# anti1_bot.net
KiCad netlist of a schematic drawn in EAGLE
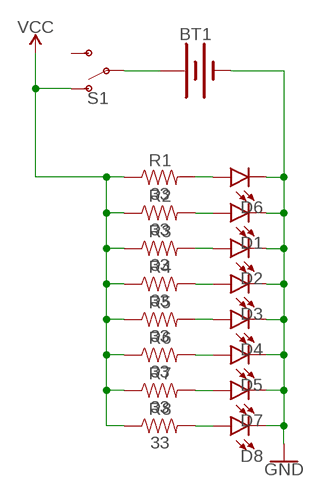
[diagram p0: schematic, sheet 1]

(export (version "E")
  (design (tool "Eeschema 10.0.6"))
  (components
    (comp (ref "BT1")
      (value "BATTERY-20MM_SMD_4LEGS")
      (footprint "eagle-import:BATTCON_20MM_4LEGS")
      (libsource (lib "eagle-import") (part "BATTERY-20MM_SMD_4LEGS"))
    )
    (comp (ref "D1")
      (value "LED0603")
      (footprint "eagle-import:LED-0603")
      (libsource (lib "eagle-import") (part "LED0603"))
    )
    (comp (ref "D2")
      (value "LED0603")
      (footprint "eagle-import:LED-0603")
      (libsource (lib "eagle-import") (part "LED0603"))
    )
    (comp (ref "D3")
      (value "LED0603")
      (footprint "eagle-import:LED-0603")
      (libsource (lib "eagle-import") (part "LED0603"))
    )
    (comp (ref "D4")
      (value "LED0603")
      (footprint "eagle-import:LED-0603")
      (libsource (lib "eagle-import") (part "LED0603"))
    )
    (comp (ref "D5")
      (value "LED0603")
      (footprint "eagle-import:LED-0603")
      (libsource (lib "eagle-import") (part "LED0603"))
    )
    (comp (ref "D6")
      (value "LED0603")
      (footprint "eagle-import:LED-0603")
      (libsource (lib "eagle-import") (part "LED0603"))
    )
    (comp (ref "D7")
      (value "LED0603")
      (footprint "eagle-import:LED-0603")
      (libsource (lib "eagle-import") (part "LED0603"))
    )
    (comp (ref "D8")
      (value "LED0603")
      (footprint "eagle-import:LED-0603")
      (libsource (lib "eagle-import") (part "LED0603"))
    )
    (comp (ref "R1")
      (value "33")
      (footprint "eagle-import:0603")
      (libsource (lib "eagle-import") (part "33OHM-0603-1/10W-1%"))
    )
    (comp (ref "R2")
      (value "33")
      (footprint "eagle-import:0603")
      (libsource (lib "eagle-import") (part "33OHM-0603-1/10W-1%"))
    )
    (comp (ref "R3")
      (value "33")
      (footprint "eagle-import:0603")
      (libsource (lib "eagle-import") (part "33OHM-0603-1/10W-1%"))
    )
    (comp (ref "R4")
      (value "33")
      (footprint "eagle-import:0603")
      (libsource (lib "eagle-import") (part "33OHM-0603-1/10W-1%"))
    )
    (comp (ref "R5")
      (value "33")
      (footprint "eagle-import:0603")
      (libsource (lib "eagle-import") (part "33OHM-0603-1/10W-1%"))
    )
    (comp (ref "R6")
      (value "33")
      (footprint "eagle-import:0603")
      (libsource (lib "eagle-import") (part "33OHM-0603-1/10W-1%"))
    )
    (comp (ref "R7")
      (value "33")
      (footprint "eagle-import:0603")
      (libsource (lib "eagle-import") (part "33OHM-0603-1/10W-1%"))
    )
    (comp (ref "R8")
      (value "33")
      (footprint "eagle-import:0603")
      (libsource (lib "eagle-import") (part "33OHM-0603-1/10W-1%"))
    )
    (comp (ref "S1")
      (value "SWITCH-SPDT-SMD-AYZ0202")
      (footprint "eagle-import:SWITCH_DPDT_SMD_AYZ0202")
      (libsource (lib "eagle-import") (part "SWITCH-SPDT-SMD-AYZ0202"))
    )
  )
  (nets
    (net (code "1") (name "GND") (class "Default")
      (node (ref "BT1") (pin "NEGATIVE") (pinfunction "-_NEGATIVE") (pintype "power_in"))
      (node (ref "D1") (pin "C") (pinfunction "C_C") (pintype "passive"))
      (node (ref "D2") (pin "C") (pinfunction "C_C") (pintype "passive"))
      (node (ref "D3") (pin "C") (pinfunction "C_C") (pintype "passive"))
      (node (ref "D4") (pin "C") (pinfunction "C_C") (pintype "passive"))
      (node (ref "D5") (pin "C") (pinfunction "C_C") (pintype "passive"))
      (node (ref "D6") (pin "C") (pinfunction "C_C") (pintype "passive"))
      (node (ref "D7") (pin "C") (pinfunction "C_C") (pintype "passive"))
      (node (ref "D8") (pin "C") (pinfunction "C_C") (pintype "passive"))
    )
    (net (code "2") (name "Net-(D1-PadA)") (class "Default")
      (node (ref "D1") (pin "A") (pinfunction "A_A") (pintype "passive"))
      (node (ref "R2") (pin "2") (pinfunction "2_2") (pintype "passive"))
    )
    (net (code "3") (name "Net-(D2-PadA)") (class "Default")
      (node (ref "D2") (pin "A") (pinfunction "A_A") (pintype "passive"))
      (node (ref "R3") (pin "2") (pinfunction "2_2") (pintype "passive"))
    )
    (net (code "4") (name "Net-(D3-PadA)") (class "Default")
      (node (ref "D3") (pin "A") (pinfunction "A_A") (pintype "passive"))
      (node (ref "R4") (pin "2") (pinfunction "2_2") (pintype "passive"))
    )
    (net (code "5") (name "Net-(D4-PadA)") (class "Default")
      (node (ref "D4") (pin "A") (pinfunction "A_A") (pintype "passive"))
      (node (ref "R5") (pin "2") (pinfunction "2_2") (pintype "passive"))
    )
    (net (code "6") (name "Net-(D5-PadA)") (class "Default")
      (node (ref "D5") (pin "A") (pinfunction "A_A") (pintype "passive"))
      (node (ref "R6") (pin "2") (pinfunction "2_2") (pintype "passive"))
    )
    (net (code "7") (name "Net-(D6-PadA)") (class "Default")
      (node (ref "D6") (pin "A") (pinfunction "A_A") (pintype "passive"))
      (node (ref "R1") (pin "2") (pinfunction "2_2") (pintype "passive"))
    )
    (net (code "8") (name "Net-(D7-PadA)") (class "Default")
      (node (ref "D7") (pin "A") (pinfunction "A_A") (pintype "passive"))
      (node (ref "R7") (pin "2") (pinfunction "2_2") (pintype "passive"))
    )
    (net (code "9") (name "Net-(D8-PadA)") (class "Default")
      (node (ref "D8") (pin "A") (pinfunction "A_A") (pintype "passive"))
      (node (ref "R8") (pin "2") (pinfunction "2_2") (pintype "passive"))
    )
    (net (code "10") (name "Net-(S1-P)") (class "Default")
      (node (ref "BT1") (pin "POSITIVE@1") (pinfunction "+_POSITIVE@1") (pintype "power_in"))
      (node (ref "BT1") (pin "POSITIVE@2") (pinfunction "+_POSITIVE@2") (pintype "power_in"))
      (node (ref "BT1") (pin "POSITIVE@3") (pinfunction "+_POSITIVE@3") (pintype "power_in"))
      (node (ref "BT1") (pin "POSITIVE@4") (pinfunction "+_POSITIVE@4") (pintype "power_in"))
      (node (ref "S1") (pin "2") (pinfunction "P_2") (pintype "passive"))
    )
    (net (code "11") (name "VCC") (class "Default")
      (node (ref "R1") (pin "1") (pinfunction "1_1") (pintype "passive"))
      (node (ref "R2") (pin "1") (pinfunction "1_1") (pintype "passive"))
      (node (ref "R3") (pin "1") (pinfunction "1_1") (pintype "passive"))
      (node (ref "R4") (pin "1") (pinfunction "1_1") (pintype "passive"))
      (node (ref "R5") (pin "1") (pinfunction "1_1") (pintype "passive"))
      (node (ref "R6") (pin "1") (pinfunction "1_1") (pintype "passive"))
      (node (ref "R7") (pin "1") (pinfunction "1_1") (pintype "passive"))
      (node (ref "R8") (pin "1") (pinfunction "1_1") (pintype "passive"))
      (node (ref "S1") (pin "1") (pinfunction "O_1") (pintype "passive"))
    )
    (net (code "12") (name "unconnected-(S1-S-Pad3)") (class "Default")
      (node (ref "S1") (pin "3") (pinfunction "S_3") (pintype "passive"))
    )
  )
)
